# CM3_Power.net
KiCad netlist of a schematic drawn in Altium Designer
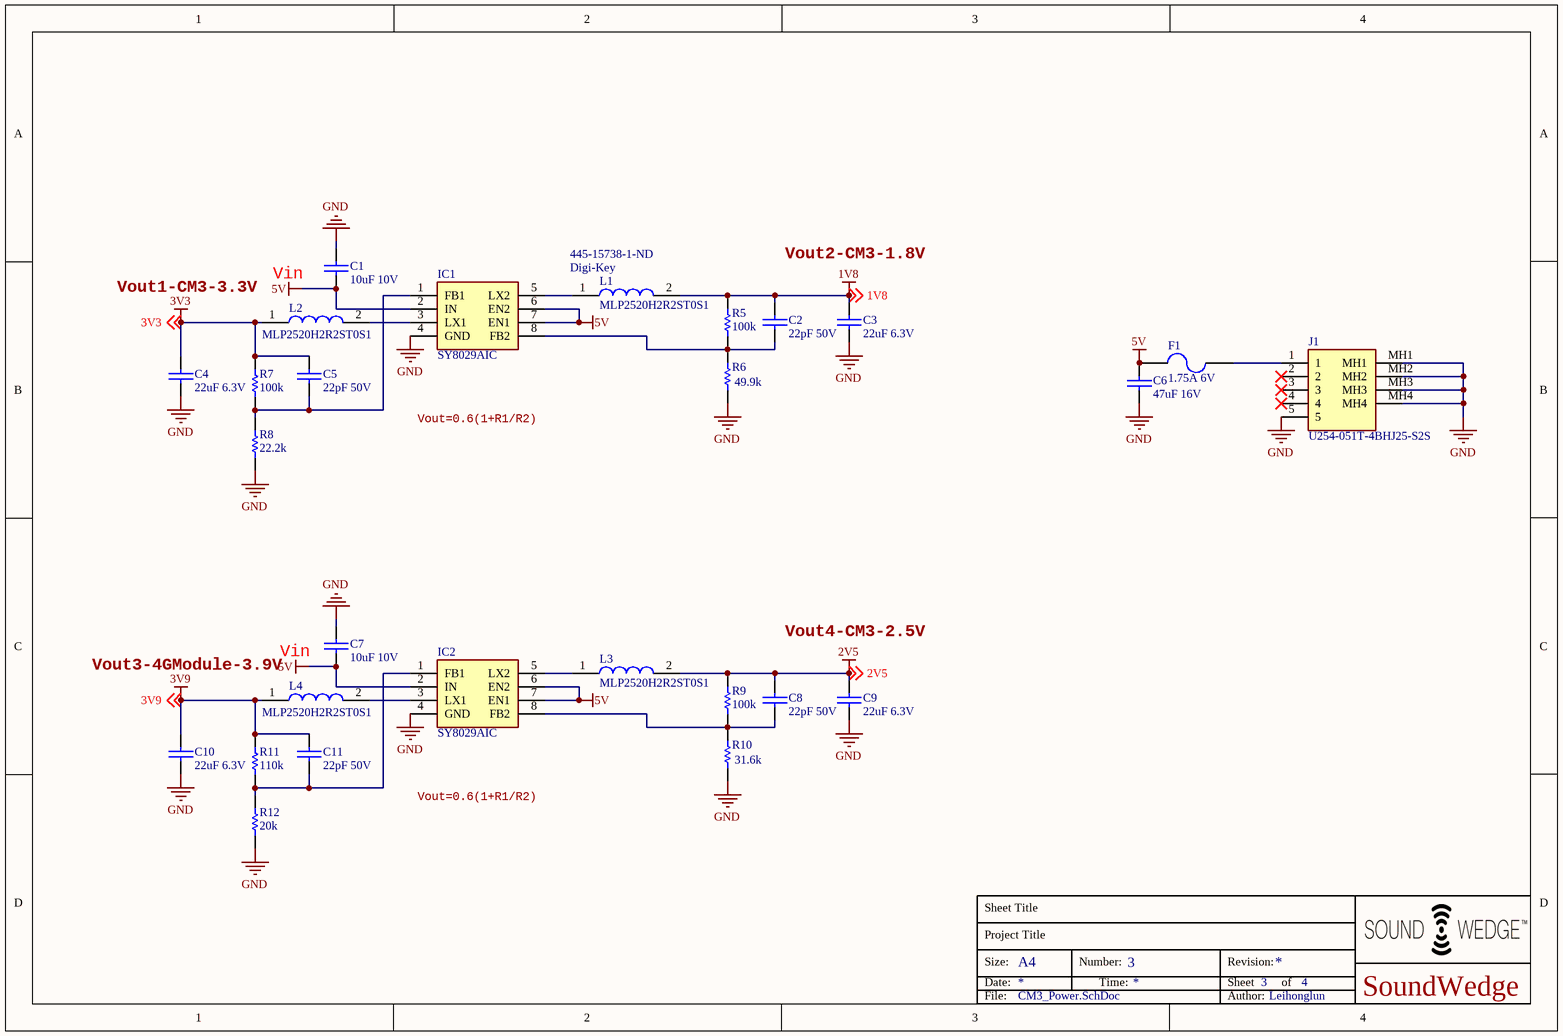
[diagram p0: CM3_Power.SchDoc]

(export (version "E")
  (design (tool "Eeschema 10.0.6"))
  (components
    (comp (ref "C1") (value "10uF 10V") (footprint "0805C") (libsource (lib "电容") (part "CAP-NP")))
    (comp (ref "C2")
      (value "22pF 50V")
      (footprint "PCB_VPlayer:0402C")
      (libsource (lib "电容") (part "CAP-NP"))
    )
    (comp (ref "C3")
      (value "22uF 6.3V")
      (footprint "PCB_VPlayer:0603C")
      (libsource (lib "电容") (part "CAP-NP"))
    )
    (comp (ref "C4")
      (value "22uF 6.3V")
      (footprint "PCB_VPlayer:0603C")
      (libsource (lib "电容") (part "CAP-NP"))
    )
    (comp (ref "C5")
      (value "22pF 50V")
      (footprint "PCB_VPlayer:0402C")
      (libsource (lib "电容") (part "CAP-NP"))
    )
    (comp (ref "C6") (value "47uF 16V") (footprint "1210C") (libsource (lib "电容") (part "CAP-NP")))
    (comp (ref "C7") (value "10uF 10V") (footprint "0805C") (libsource (lib "电容") (part "CAP-NP")))
    (comp (ref "C8")
      (value "22pF 50V")
      (footprint "PCB_VPlayer:0402C")
      (libsource (lib "电容") (part "CAP-NP"))
    )
    (comp (ref "C9")
      (value "22uF 6.3V")
      (footprint "PCB_VPlayer:0603C")
      (libsource (lib "电容") (part "CAP-NP"))
    )
    (comp (ref "C10")
      (value "22uF 6.3V")
      (footprint "PCB_VPlayer:0603C")
      (libsource (lib "电容") (part "CAP-NP"))
    )
    (comp (ref "C11")
      (value "22pF 50V")
      (footprint "PCB_VPlayer:0402C")
      (libsource (lib "电容") (part "CAP-NP"))
    )
    (comp (ref "F1") (value "1.75A 6V") (footprint "FUSE-1210") (libsource (lib "保险丝") (part "FUSE")))
    (comp (ref "IC1")
      (value "SY8029AIC")
      (footprint "SamacSys:SOT65P280X110-8N")
      (description "Integrated Circuit")
      (libsource (lib "*") (part "SY8029AIC"))
    )
    (comp (ref "IC2")
      (value "SY8029AIC")
      (footprint "SamacSys:SOT65P280X110-8N")
      (description "Integrated Circuit")
      (libsource (lib "*") (part "SY8029AIC"))
    )
    (comp (ref "J1")
      (value "U254-051T-4BHJ25-S2S")
      (footprint "SamacSys:U254051T4BHJ25S2S")
      (description "Connector")
      (libsource (lib "*") (part "U254-051T-4BHJ25-S2S"))
    )
    (comp (ref "L1")
      (value "MLP2520H2R2ST0S1")
      (footprint "SamacSys:INDC2520X100N")
      (description "Inductor")
      (fields
        (field (name "MANUFACTURER_PART_NUMBER") "MLP2520K1R0MT0S1")
        (field (name "MOUSER PART NUMBER") "810-MLP2520K1R0MT0S1")
        (field (name "SUPPLIER 1") "Digi-Key")
        (field (name "SUPPLIER PART NUMBER 1") "445-15738-1-ND")
      )
      (libsource (lib "*") (part "MLP2520K1R0MT0S1"))
    )
    (comp (ref "L2")
      (value "MLP2520H2R2ST0S1")
      (footprint "SamacSys:INDC2520X100N")
      (description "Inductor")
      (fields
        (field (name "MANUFACTURER_PART_NUMBER") "MLP2520K1R0MT0S1")
        (field (name "MOUSER PART NUMBER") "810-MLP2520K1R0MT0S1")
      )
      (libsource (lib "*") (part "MLP2520K1R0MT0S1"))
    )
    (comp (ref "L3")
      (value "MLP2520H2R2ST0S1")
      (footprint "SamacSys:INDC2520X100N")
      (description "Inductor")
      (fields
        (field (name "MANUFACTURER_PART_NUMBER") "MLP2520K1R0MT0S1")
        (field (name "MOUSER PART NUMBER") "810-MLP2520K1R0MT0S1")
      )
      (libsource (lib "*") (part "MLP2520K1R0MT0S1"))
    )
    (comp (ref "L4")
      (value "MLP2520H2R2ST0S1")
      (footprint "SamacSys:INDC2520X100N")
      (description "Inductor")
      (fields
        (field (name "MANUFACTURER_PART_NUMBER") "MLP2520K1R0MT0S1")
        (field (name "MOUSER PART NUMBER") "810-MLP2520K1R0MT0S1")
      )
      (libsource (lib "*") (part "MLP2520K1R0MT0S1"))
    )
    (comp (ref "R5") (value "100k") (footprint "PCB_VPlayer:0402R") (libsource (lib "电阻") (part "RES")))
    (comp (ref "R6") (value "49.9k") (footprint "PCB_VPlayer:0402R") (libsource (lib "电阻") (part "RES")))
    (comp (ref "R7") (value "100k") (footprint "PCB_VPlayer:0402R") (libsource (lib "电阻") (part "RES")))
    (comp (ref "R8") (value "22.2k") (footprint "PCB_VPlayer:0402R") (libsource (lib "电阻") (part "RES")))
    (comp (ref "R9") (value "100k") (footprint "PCB_VPlayer:0402R") (libsource (lib "电阻") (part "RES")))
    (comp (ref "R10") (value "31.6k") (footprint "PCB_VPlayer:0402R") (libsource (lib "电阻") (part "RES")))
    (comp (ref "R11") (value "110k") (footprint "PCB_VPlayer:0402R") (libsource (lib "电阻") (part "RES")))
    (comp (ref "R12") (value "20k") (footprint "PCB_VPlayer:0402R") (libsource (lib "电阻") (part "RES")))
  )
  (nets
    (net (code "1") (name "1V8") (class "Default")
      (node (ref "C2") (pin "2") (pinfunction "2_2") (pintype "passive"))
      (node (ref "C3") (pin "2") (pinfunction "2_2") (pintype "passive"))
      (node (ref "L1") (pin "2") (pinfunction "2_2") (pintype "passive"))
      (node (ref "R5") (pin "2") (pinfunction "2_2") (pintype "passive"))
    )
    (net (code "2") (name "2V5") (class "Default")
      (node (ref "C8") (pin "2") (pinfunction "2_2") (pintype "passive"))
      (node (ref "C9") (pin "2") (pinfunction "2_2") (pintype "passive"))
      (node (ref "L3") (pin "2") (pinfunction "2_2") (pintype "passive"))
      (node (ref "R9") (pin "2") (pinfunction "2_2") (pintype "passive"))
    )
    (net (code "3") (name "3V3") (class "Default")
      (node (ref "C4") (pin "2") (pinfunction "2_2") (pintype "passive"))
      (node (ref "C5") (pin "2") (pinfunction "2_2") (pintype "passive"))
      (node (ref "L2") (pin "1") (pinfunction "1_1") (pintype "passive"))
      (node (ref "R7") (pin "2") (pinfunction "2_2") (pintype "passive"))
    )
    (net (code "4") (name "3V9") (class "Default")
      (node (ref "C10") (pin "2") (pinfunction "2_2") (pintype "passive"))
      (node (ref "C11") (pin "2") (pinfunction "2_2") (pintype "passive"))
      (node (ref "L4") (pin "1") (pinfunction "1_1") (pintype "passive"))
      (node (ref "R11") (pin "2") (pinfunction "2_2") (pintype "passive"))
    )
    (net (code "5") (name "5V") (class "Default")
      (node (ref "C1") (pin "1") (pinfunction "1_1") (pintype "passive"))
      (node (ref "C6") (pin "2") (pinfunction "2_2") (pintype "passive"))
      (node (ref "C7") (pin "1") (pinfunction "1_1") (pintype "passive"))
      (node (ref "F1") (pin "1") (pinfunction "1_1") (pintype "passive"))
      (node (ref "IC1") (pin "2") (pinfunction "IN_2") (pintype "passive"))
      (node (ref "IC1") (pin "6") (pinfunction "EN2_6") (pintype "passive"))
      (node (ref "IC1") (pin "7") (pinfunction "EN1_7") (pintype "passive"))
      (node (ref "IC2") (pin "2") (pinfunction "IN_2") (pintype "passive"))
      (node (ref "IC2") (pin "6") (pinfunction "EN2_6") (pintype "passive"))
      (node (ref "IC2") (pin "7") (pinfunction "EN1_7") (pintype "passive"))
    )
    (net (code "6") (name "GND") (class "Default")
      (node (ref "C1") (pin "2") (pinfunction "2_2") (pintype "passive"))
      (node (ref "C10") (pin "1") (pinfunction "1_1") (pintype "passive"))
      (node (ref "C3") (pin "1") (pinfunction "1_1") (pintype "passive"))
      (node (ref "C4") (pin "1") (pinfunction "1_1") (pintype "passive"))
      (node (ref "C6") (pin "1") (pinfunction "1_1") (pintype "passive"))
      (node (ref "C7") (pin "2") (pinfunction "2_2") (pintype "passive"))
      (node (ref "C9") (pin "1") (pinfunction "1_1") (pintype "passive"))
      (node (ref "IC1") (pin "4") (pinfunction "GND_4") (pintype "passive"))
      (node (ref "IC2") (pin "4") (pinfunction "GND_4") (pintype "passive"))
      (node (ref "J1") (pin "5") (pinfunction "5_5") (pintype "passive"))
      (node (ref "J1") (pin "MH1") (pinfunction "MH1_MH1") (pintype "passive"))
      (node (ref "J1") (pin "MH2") (pinfunction "MH2_MH2") (pintype "passive"))
      (node (ref "J1") (pin "MH3") (pinfunction "MH3_MH3") (pintype "passive"))
      (node (ref "J1") (pin "MH4") (pinfunction "MH4_MH4") (pintype "passive"))
      (node (ref "R10") (pin "1") (pinfunction "1_1") (pintype "passive"))
      (node (ref "R12") (pin "1") (pinfunction "1_1") (pintype "passive"))
      (node (ref "R6") (pin "1") (pinfunction "1_1") (pintype "passive"))
      (node (ref "R8") (pin "1") (pinfunction "1_1") (pintype "passive"))
    )
    (net (code "7") (name "Net-(F1-Pad2)") (class "Default")
      (node (ref "F1") (pin "2") (pinfunction "2_2") (pintype "passive"))
      (node (ref "J1") (pin "1") (pinfunction "1_1") (pintype "passive"))
    )
    (net (code "8") (name "Net-(IC1-FB1)") (class "Default")
      (node (ref "C5") (pin "1") (pinfunction "1_1") (pintype "passive"))
      (node (ref "IC1") (pin "1") (pinfunction "FB1_1") (pintype "passive"))
      (node (ref "R7") (pin "1") (pinfunction "1_1") (pintype "passive"))
      (node (ref "R8") (pin "2") (pinfunction "2_2") (pintype "passive"))
    )
    (net (code "9") (name "Net-(IC1-FB2)") (class "Default")
      (node (ref "C2") (pin "1") (pinfunction "1_1") (pintype "passive"))
      (node (ref "IC1") (pin "8") (pinfunction "FB2_8") (pintype "passive"))
      (node (ref "R5") (pin "1") (pinfunction "1_1") (pintype "passive"))
      (node (ref "R6") (pin "2") (pinfunction "2_2") (pintype "passive"))
    )
    (net (code "10") (name "Net-(IC1-LX1)") (class "Default")
      (node (ref "IC1") (pin "3") (pinfunction "LX1_3") (pintype "passive"))
      (node (ref "L2") (pin "2") (pinfunction "2_2") (pintype "passive"))
    )
    (net (code "11") (name "Net-(IC1-LX2)") (class "Default")
      (node (ref "IC1") (pin "5") (pinfunction "LX2_5") (pintype "passive"))
      (node (ref "L1") (pin "1") (pinfunction "1_1") (pintype "passive"))
    )
    (net (code "12") (name "Net-(IC2-FB1)") (class "Default")
      (node (ref "C11") (pin "1") (pinfunction "1_1") (pintype "passive"))
      (node (ref "IC2") (pin "1") (pinfunction "FB1_1") (pintype "passive"))
      (node (ref "R11") (pin "1") (pinfunction "1_1") (pintype "passive"))
      (node (ref "R12") (pin "2") (pinfunction "2_2") (pintype "passive"))
    )
    (net (code "13") (name "Net-(IC2-FB2)") (class "Default")
      (node (ref "C8") (pin "1") (pinfunction "1_1") (pintype "passive"))
      (node (ref "IC2") (pin "8") (pinfunction "FB2_8") (pintype "passive"))
      (node (ref "R10") (pin "2") (pinfunction "2_2") (pintype "passive"))
      (node (ref "R9") (pin "1") (pinfunction "1_1") (pintype "passive"))
    )
    (net (code "14") (name "Net-(IC2-LX1)") (class "Default")
      (node (ref "IC2") (pin "3") (pinfunction "LX1_3") (pintype "passive"))
      (node (ref "L4") (pin "2") (pinfunction "2_2") (pintype "passive"))
    )
    (net (code "15") (name "Net-(IC2-LX2)") (class "Default")
      (node (ref "IC2") (pin "5") (pinfunction "LX2_5") (pintype "passive"))
      (node (ref "L3") (pin "1") (pinfunction "1_1") (pintype "passive"))
    )
    (net (code "16") (name "unconnected-(J1-Pad2)") (class "Default")
      (node (ref "J1") (pin "2") (pinfunction "2_2") (pintype "passive+no_connect"))
    )
    (net (code "17") (name "unconnected-(J1-Pad3)") (class "Default")
      (node (ref "J1") (pin "3") (pinfunction "3_3") (pintype "passive+no_connect"))
    )
    (net (code "18") (name "unconnected-(J1-Pad4)") (class "Default")
      (node (ref "J1") (pin "4") (pinfunction "4_4") (pintype "passive+no_connect"))
    )
  )
)
